# adder_fpga.net
KiCad netlist of a schematic drawn in EAGLE
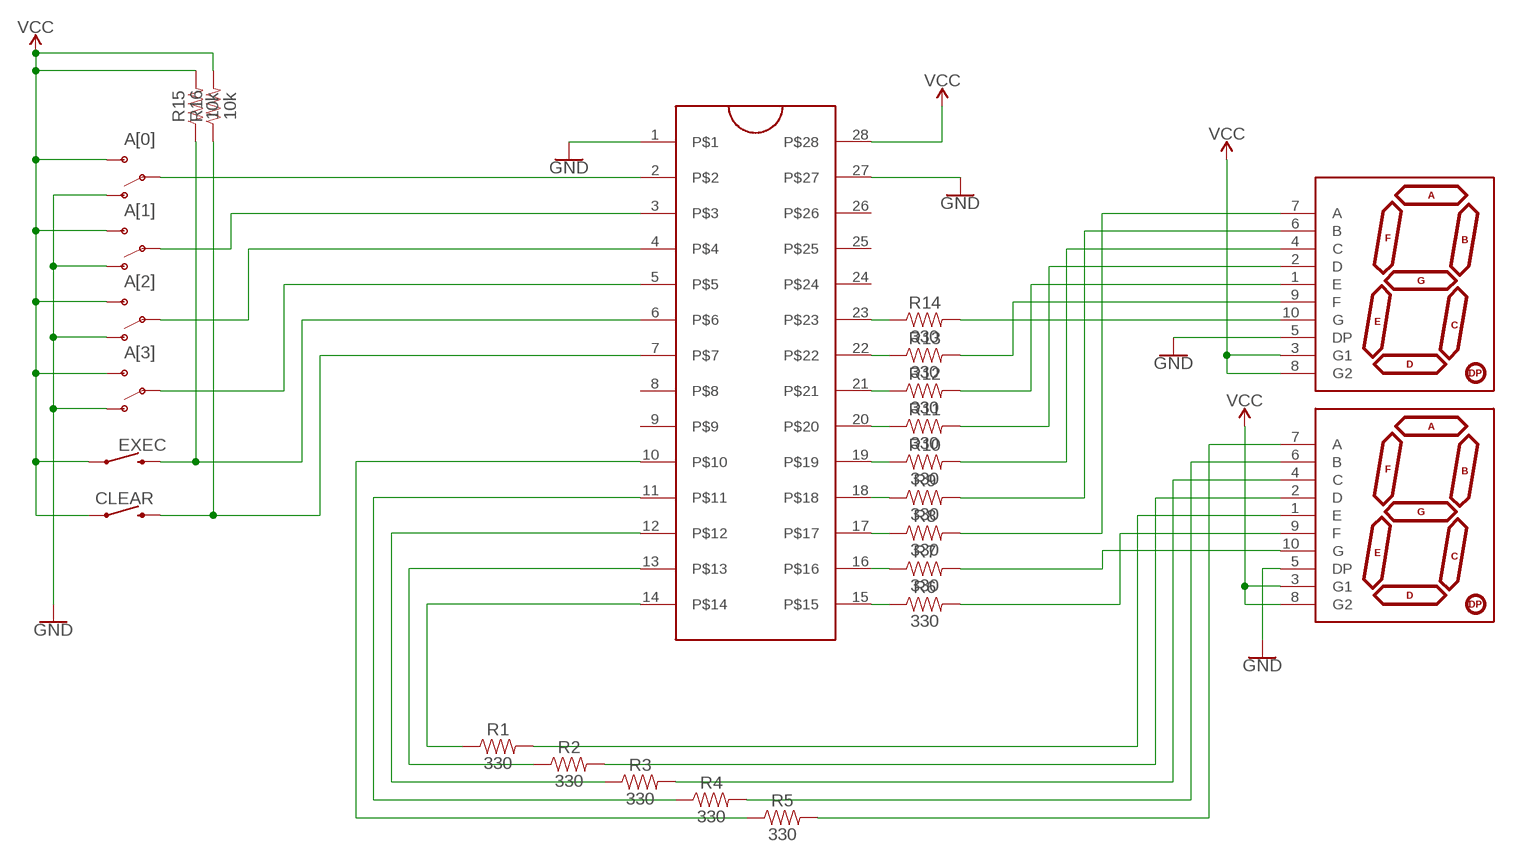
[diagram p0: schematic, sheet 1]

(export (version "E")
  (design (tool "Eeschema 10.0.6"))
  (components
    (comp (ref "A[0]")
      (value "SWITCH-SPDT-PTH-11.6X4.0MM")
      (footprint "eagle-import:SWITCH_SPDT_PTH_11.6X4.0MM")
      (libsource (lib "eagle-import") (part "SWITCH-SPDT-PTH-11.6X4.0MM"))
    )
    (comp (ref "A[1]")
      (value "SWITCH-SPDT-PTH-11.6X4.0MM")
      (footprint "eagle-import:SWITCH_SPDT_PTH_11.6X4.0MM")
      (libsource (lib "eagle-import") (part "SWITCH-SPDT-PTH-11.6X4.0MM"))
    )
    (comp (ref "A[2]")
      (value "SWITCH-SPDT-PTH-11.6X4.0MM")
      (footprint "eagle-import:SWITCH_SPDT_PTH_11.6X4.0MM")
      (libsource (lib "eagle-import") (part "SWITCH-SPDT-PTH-11.6X4.0MM"))
    )
    (comp (ref "A[3]")
      (value "SWITCH-SPDT-PTH-11.6X4.0MM")
      (footprint "eagle-import:SWITCH_SPDT_PTH_11.6X4.0MM")
      (libsource (lib "eagle-import") (part "SWITCH-SPDT-PTH-11.6X4.0MM"))
    )
    (comp (ref "CLEAR")
      (value "MOMENTARY-SWITCH-SPST-PTH-6.0MM")
      (footprint "eagle-import:TACTILE_SWITCH_PTH_6.0MM")
      (libsource (lib "eagle-import") (part "MOMENTARY-SWITCH-SPST-PTH-6.0MM"))
    )
    (comp (ref "EXEC")
      (value "MOMENTARY-SWITCH-SPST-PTH-6.0MM")
      (footprint "eagle-import:TACTILE_SWITCH_PTH_6.0MM")
      (libsource (lib "eagle-import") (part "MOMENTARY-SWITCH-SPST-PTH-6.0MM"))
    )
    (comp (ref "J1")
      (value "ZIFSOCKET-28-3\"")
      (footprint "eagle-import:DIL28-3-ZIF_SOCKET")
      (libsource (lib "eagle-import") (part "ZIFSOCKET-28-3{dblquote}"))
    )
    (comp (ref "R1")
      (value "330")
      (footprint "eagle-import:AXIAL-0.3")
      (libsource (lib "eagle-import") (part "330OHM-HORIZ-1/10W-5%"))
    )
    (comp (ref "R2")
      (value "330")
      (footprint "eagle-import:AXIAL-0.3")
      (libsource (lib "eagle-import") (part "330OHM-HORIZ-1/10W-5%"))
    )
    (comp (ref "R3")
      (value "330")
      (footprint "eagle-import:AXIAL-0.3")
      (libsource (lib "eagle-import") (part "330OHM-HORIZ-1/10W-5%"))
    )
    (comp (ref "R4")
      (value "330")
      (footprint "eagle-import:AXIAL-0.3")
      (libsource (lib "eagle-import") (part "330OHM-HORIZ-1/10W-5%"))
    )
    (comp (ref "R5")
      (value "330")
      (footprint "eagle-import:AXIAL-0.3")
      (libsource (lib "eagle-import") (part "330OHM-HORIZ-1/10W-5%"))
    )
    (comp (ref "R6")
      (value "330")
      (footprint "eagle-import:AXIAL-0.3")
      (libsource (lib "eagle-import") (part "330OHM-HORIZ-1/10W-5%"))
    )
    (comp (ref "R7")
      (value "330")
      (footprint "eagle-import:AXIAL-0.3")
      (libsource (lib "eagle-import") (part "330OHM-HORIZ-1/10W-5%"))
    )
    (comp (ref "R8")
      (value "330")
      (footprint "eagle-import:AXIAL-0.3")
      (libsource (lib "eagle-import") (part "330OHM-HORIZ-1/10W-5%"))
    )
    (comp (ref "R9")
      (value "330")
      (footprint "eagle-import:AXIAL-0.3")
      (libsource (lib "eagle-import") (part "330OHM-HORIZ-1/10W-5%"))
    )
    (comp (ref "R10")
      (value "330")
      (footprint "eagle-import:AXIAL-0.3")
      (libsource (lib "eagle-import") (part "330OHM-HORIZ-1/10W-5%"))
    )
    (comp (ref "R11")
      (value "330")
      (footprint "eagle-import:AXIAL-0.3")
      (libsource (lib "eagle-import") (part "330OHM-HORIZ-1/10W-5%"))
    )
    (comp (ref "R12")
      (value "330")
      (footprint "eagle-import:AXIAL-0.3")
      (libsource (lib "eagle-import") (part "330OHM-HORIZ-1/10W-5%"))
    )
    (comp (ref "R13")
      (value "330")
      (footprint "eagle-import:AXIAL-0.3")
      (libsource (lib "eagle-import") (part "330OHM-HORIZ-1/10W-5%"))
    )
    (comp (ref "R14")
      (value "330")
      (footprint "eagle-import:AXIAL-0.3")
      (libsource (lib "eagle-import") (part "330OHM-HORIZ-1/10W-5%"))
    )
    (comp (ref "R15")
      (value "10k")
      (footprint "eagle-import:AXIAL-0.3")
      (libsource (lib "eagle-import") (part "10KOHM-HORIZ-1/4W-1%"))
    )
    (comp (ref "R16")
      (value "10k")
      (footprint "eagle-import:AXIAL-0.3")
      (libsource (lib "eagle-import") (part "10KOHM-HORIZ-1/4W-1%"))
    )
    (comp (ref "U$1")
      (value "YSD-1601AR4B-8")
      (footprint "eagle-import:7-SEGMENT-1_PTH")
      (libsource (lib "eagle-import") (part "7-SEGMENT-1DIGIT-1INCH-RED"))
    )
    (comp (ref "U$2")
      (value "YSD-1601AR4B-8")
      (footprint "eagle-import:7-SEGMENT-1_PTH")
      (libsource (lib "eagle-import") (part "7-SEGMENT-1DIGIT-1INCH-RED"))
    )
  )
  (nets
    (net (code "1") (name "GND") (class "Default")
      (node (ref "A[0]") (pin "1") (pinfunction "O_1") (pintype "passive"))
      (node (ref "A[1]") (pin "1") (pinfunction "O_1") (pintype "passive"))
      (node (ref "A[2]") (pin "1") (pinfunction "O_1") (pintype "passive"))
      (node (ref "A[3]") (pin "1") (pinfunction "O_1") (pintype "passive"))
      (node (ref "J1") (pin "1") (pinfunction "P$1_1") (pintype "bidirectional"))
      (node (ref "J1") (pin "27") (pinfunction "P$27_27") (pintype "bidirectional"))
      (node (ref "U$1") (pin "5") (pinfunction "DP_5") (pintype "bidirectional"))
      (node (ref "U$2") (pin "5") (pinfunction "DP_5") (pintype "bidirectional"))
    )
    (net (code "2") (name "Net-(A[0]-P)") (class "Default")
      (node (ref "A[0]") (pin "2") (pinfunction "P_2") (pintype "passive"))
      (node (ref "J1") (pin "2") (pinfunction "P$2_2") (pintype "bidirectional"))
    )
    (net (code "3") (name "Net-(A[1]-P)") (class "Default")
      (node (ref "A[1]") (pin "2") (pinfunction "P_2") (pintype "passive"))
      (node (ref "J1") (pin "3") (pinfunction "P$3_3") (pintype "bidirectional"))
    )
    (net (code "4") (name "Net-(A[2]-P)") (class "Default")
      (node (ref "A[2]") (pin "2") (pinfunction "P_2") (pintype "passive"))
      (node (ref "J1") (pin "4") (pinfunction "P$4_4") (pintype "bidirectional"))
    )
    (net (code "5") (name "Net-(A[3]-P)") (class "Default")
      (node (ref "A[3]") (pin "2") (pinfunction "P_2") (pintype "passive"))
      (node (ref "J1") (pin "5") (pinfunction "P$5_5") (pintype "bidirectional"))
    )
    (net (code "6") (name "Net-(CLEAR-2)") (class "Default")
      (node (ref "CLEAR") (pin "3") (pinfunction "2_3") (pintype "passive"))
      (node (ref "J1") (pin "7") (pinfunction "P$7_7") (pintype "bidirectional"))
      (node (ref "R16") (pin "P$1") (pinfunction "1_P$1") (pintype "passive"))
    )
    (net (code "7") (name "Net-(EXEC-2)") (class "Default")
      (node (ref "EXEC") (pin "3") (pinfunction "2_3") (pintype "passive"))
      (node (ref "J1") (pin "6") (pinfunction "P$6_6") (pintype "bidirectional"))
      (node (ref "R15") (pin "P$1") (pinfunction "1_P$1") (pintype "passive"))
    )
    (net (code "8") (name "Net-(J1-P$10)") (class "Default")
      (node (ref "J1") (pin "10") (pinfunction "P$10_10") (pintype "bidirectional"))
      (node (ref "R5") (pin "P$1") (pinfunction "1_P$1") (pintype "passive"))
    )
    (net (code "9") (name "Net-(J1-P$11)") (class "Default")
      (node (ref "J1") (pin "11") (pinfunction "P$11_11") (pintype "bidirectional"))
      (node (ref "R4") (pin "P$1") (pinfunction "1_P$1") (pintype "passive"))
    )
    (net (code "10") (name "Net-(J1-P$12)") (class "Default")
      (node (ref "J1") (pin "12") (pinfunction "P$12_12") (pintype "bidirectional"))
      (node (ref "R3") (pin "P$1") (pinfunction "1_P$1") (pintype "passive"))
    )
    (net (code "11") (name "Net-(J1-P$13)") (class "Default")
      (node (ref "J1") (pin "13") (pinfunction "P$13_13") (pintype "bidirectional"))
      (node (ref "R2") (pin "P$1") (pinfunction "1_P$1") (pintype "passive"))
    )
    (net (code "12") (name "Net-(J1-P$14)") (class "Default")
      (node (ref "J1") (pin "14") (pinfunction "P$14_14") (pintype "bidirectional"))
      (node (ref "R1") (pin "P$1") (pinfunction "1_P$1") (pintype "passive"))
    )
    (net (code "13") (name "Net-(J1-P$15)") (class "Default")
      (node (ref "J1") (pin "15") (pinfunction "P$15_15") (pintype "bidirectional"))
      (node (ref "R6") (pin "P$1") (pinfunction "1_P$1") (pintype "passive"))
    )
    (net (code "14") (name "Net-(J1-P$16)") (class "Default")
      (node (ref "J1") (pin "16") (pinfunction "P$16_16") (pintype "bidirectional"))
      (node (ref "R7") (pin "P$1") (pinfunction "1_P$1") (pintype "passive"))
    )
    (net (code "15") (name "Net-(J1-P$17)") (class "Default")
      (node (ref "J1") (pin "17") (pinfunction "P$17_17") (pintype "bidirectional"))
      (node (ref "R8") (pin "P$1") (pinfunction "1_P$1") (pintype "passive"))
    )
    (net (code "16") (name "Net-(J1-P$18)") (class "Default")
      (node (ref "J1") (pin "18") (pinfunction "P$18_18") (pintype "bidirectional"))
      (node (ref "R9") (pin "P$1") (pinfunction "1_P$1") (pintype "passive"))
    )
    (net (code "17") (name "Net-(J1-P$19)") (class "Default")
      (node (ref "J1") (pin "19") (pinfunction "P$19_19") (pintype "bidirectional"))
      (node (ref "R10") (pin "P$1") (pinfunction "1_P$1") (pintype "passive"))
    )
    (net (code "18") (name "Net-(J1-P$20)") (class "Default")
      (node (ref "J1") (pin "20") (pinfunction "P$20_20") (pintype "bidirectional"))
      (node (ref "R11") (pin "P$1") (pinfunction "1_P$1") (pintype "passive"))
    )
    (net (code "19") (name "Net-(J1-P$21)") (class "Default")
      (node (ref "J1") (pin "21") (pinfunction "P$21_21") (pintype "bidirectional"))
      (node (ref "R12") (pin "P$1") (pinfunction "1_P$1") (pintype "passive"))
    )
    (net (code "20") (name "Net-(J1-P$22)") (class "Default")
      (node (ref "J1") (pin "22") (pinfunction "P$22_22") (pintype "bidirectional"))
      (node (ref "R13") (pin "P$1") (pinfunction "1_P$1") (pintype "passive"))
    )
    (net (code "21") (name "Net-(J1-P$23)") (class "Default")
      (node (ref "J1") (pin "23") (pinfunction "P$23_23") (pintype "bidirectional"))
      (node (ref "R14") (pin "P$1") (pinfunction "1_P$1") (pintype "passive"))
    )
    (net (code "22") (name "Net-(R1-2)") (class "Default")
      (node (ref "R1") (pin "P$2") (pinfunction "2_P$2") (pintype "passive"))
      (node (ref "U$2") (pin "1") (pinfunction "E_1") (pintype "bidirectional"))
    )
    (net (code "23") (name "Net-(R2-2)") (class "Default")
      (node (ref "R2") (pin "P$2") (pinfunction "2_P$2") (pintype "passive"))
      (node (ref "U$2") (pin "2") (pinfunction "D_2") (pintype "bidirectional"))
    )
    (net (code "24") (name "Net-(R3-2)") (class "Default")
      (node (ref "R3") (pin "P$2") (pinfunction "2_P$2") (pintype "passive"))
      (node (ref "U$2") (pin "4") (pinfunction "C_4") (pintype "bidirectional"))
    )
    (net (code "25") (name "Net-(R4-2)") (class "Default")
      (node (ref "R4") (pin "P$2") (pinfunction "2_P$2") (pintype "passive"))
      (node (ref "U$2") (pin "6") (pinfunction "B_6") (pintype "bidirectional"))
    )
    (net (code "26") (name "Net-(R5-2)") (class "Default")
      (node (ref "R5") (pin "P$2") (pinfunction "2_P$2") (pintype "passive"))
      (node (ref "U$2") (pin "7") (pinfunction "A_7") (pintype "bidirectional"))
    )
    (net (code "27") (name "Net-(R6-2)") (class "Default")
      (node (ref "R6") (pin "P$2") (pinfunction "2_P$2") (pintype "passive"))
      (node (ref "U$2") (pin "9") (pinfunction "F_9") (pintype "bidirectional"))
    )
    (net (code "28") (name "Net-(R7-2)") (class "Default")
      (node (ref "R7") (pin "P$2") (pinfunction "2_P$2") (pintype "passive"))
      (node (ref "U$2") (pin "10") (pinfunction "G_10") (pintype "bidirectional"))
    )
    (net (code "29") (name "Net-(R8-2)") (class "Default")
      (node (ref "R8") (pin "P$2") (pinfunction "2_P$2") (pintype "passive"))
      (node (ref "U$1") (pin "7") (pinfunction "A_7") (pintype "bidirectional"))
    )
    (net (code "30") (name "Net-(R9-2)") (class "Default")
      (node (ref "R9") (pin "P$2") (pinfunction "2_P$2") (pintype "passive"))
      (node (ref "U$1") (pin "6") (pinfunction "B_6") (pintype "bidirectional"))
    )
    (net (code "31") (name "Net-(R10-2)") (class "Default")
      (node (ref "R10") (pin "P$2") (pinfunction "2_P$2") (pintype "passive"))
      (node (ref "U$1") (pin "4") (pinfunction "C_4") (pintype "bidirectional"))
    )
    (net (code "32") (name "Net-(R11-2)") (class "Default")
      (node (ref "R11") (pin "P$2") (pinfunction "2_P$2") (pintype "passive"))
      (node (ref "U$1") (pin "2") (pinfunction "D_2") (pintype "bidirectional"))
    )
    (net (code "33") (name "Net-(R12-2)") (class "Default")
      (node (ref "R12") (pin "P$2") (pinfunction "2_P$2") (pintype "passive"))
      (node (ref "U$1") (pin "1") (pinfunction "E_1") (pintype "bidirectional"))
    )
    (net (code "34") (name "Net-(R13-2)") (class "Default")
      (node (ref "R13") (pin "P$2") (pinfunction "2_P$2") (pintype "passive"))
      (node (ref "U$1") (pin "9") (pinfunction "F_9") (pintype "bidirectional"))
    )
    (net (code "35") (name "Net-(R14-2)") (class "Default")
      (node (ref "R14") (pin "P$2") (pinfunction "2_P$2") (pintype "passive"))
      (node (ref "U$1") (pin "10") (pinfunction "G_10") (pintype "bidirectional"))
    )
    (net (code "36") (name "VCC") (class "Default")
      (node (ref "A[0]") (pin "3") (pinfunction "S_3") (pintype "passive"))
      (node (ref "A[1]") (pin "3") (pinfunction "S_3") (pintype "passive"))
      (node (ref "A[2]") (pin "3") (pinfunction "S_3") (pintype "passive"))
      (node (ref "A[3]") (pin "3") (pinfunction "S_3") (pintype "passive"))
      (node (ref "CLEAR") (pin "1") (pinfunction "1_1") (pintype "passive"))
      (node (ref "EXEC") (pin "1") (pinfunction "1_1") (pintype "passive"))
      (node (ref "J1") (pin "28") (pinfunction "P$28_28") (pintype "bidirectional"))
      (node (ref "R15") (pin "P$2") (pinfunction "2_P$2") (pintype "passive"))
      (node (ref "R16") (pin "P$2") (pinfunction "2_P$2") (pintype "passive"))
      (node (ref "U$1") (pin "3") (pinfunction "G1_3") (pintype "bidirectional"))
      (node (ref "U$1") (pin "8") (pinfunction "G2_8") (pintype "bidirectional"))
      (node (ref "U$2") (pin "3") (pinfunction "G1_3") (pintype "bidirectional"))
      (node (ref "U$2") (pin "8") (pinfunction "G2_8") (pintype "bidirectional"))
    )
    (net (code "37") (name "unconnected-(J1-P$8-Pad8)") (class "Default")
      (node (ref "J1") (pin "8") (pinfunction "P$8_8") (pintype "bidirectional"))
    )
    (net (code "38") (name "unconnected-(J1-P$9-Pad9)") (class "Default")
      (node (ref "J1") (pin "9") (pinfunction "P$9_9") (pintype "bidirectional"))
    )
    (net (code "39") (name "unconnected-(J1-P$24-Pad24)") (class "Default")
      (node (ref "J1") (pin "24") (pinfunction "P$24_24") (pintype "bidirectional"))
    )
    (net (code "40") (name "unconnected-(J1-P$25-Pad25)") (class "Default")
      (node (ref "J1") (pin "25") (pinfunction "P$25_25") (pintype "bidirectional"))
    )
    (net (code "41") (name "unconnected-(J1-P$26-Pad26)") (class "Default")
      (node (ref "J1") (pin "26") (pinfunction "P$26_26") (pintype "bidirectional"))
    )
  )
)
